# Analog_Project_Sem_3.net
KiCad netlist of a schematic drawn in Altium Designer
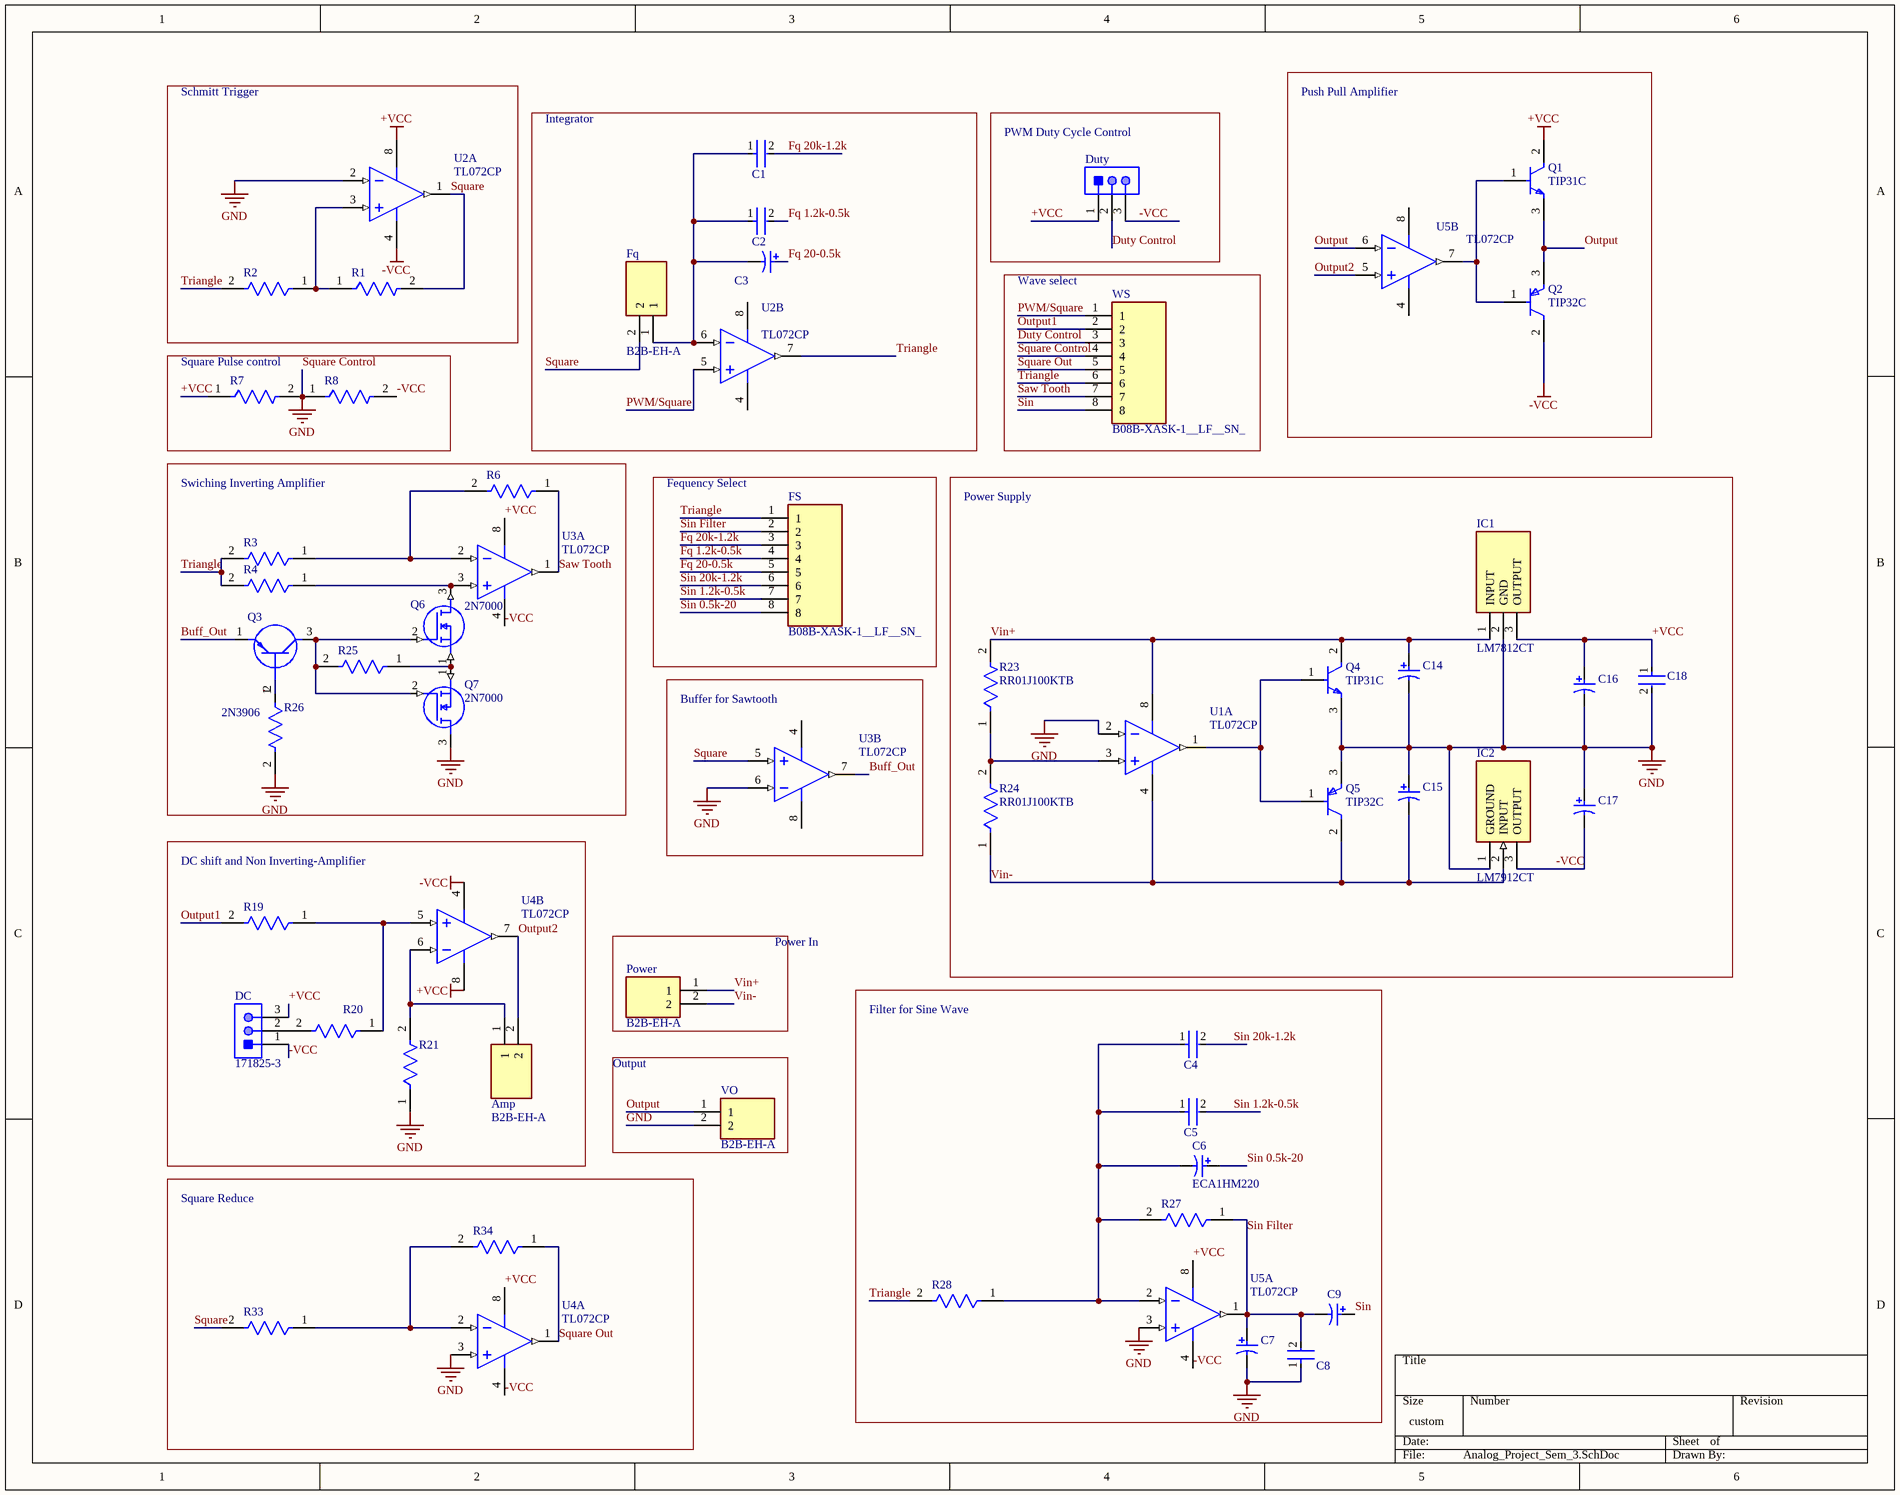
[diagram p0: Analog_Project_Sem_3.SchDoc]

(export (version "E")
  (design (tool "Eeschema 10.0.6"))
  (components
    (comp (ref "Amp")
      (value "B2B-EH-A")
      (footprint "SamacSys:SHDR2W64P0X250_1X2_750X380X600P")
      (description "Connector")
      (libsource (lib "") (part "B2B-EH-A_2"))
    )
    (comp (ref "C1")
      (value "RCER72A104K1A2H03B")
      (footprint "FP-RCE1A2-MFG")
      (description "Cap Ceramic 100nF 100V X7R ±10% Radial 2.5mm +125°C Automotive Bulk")
      (fields (field (name "TOLERANCE") "10%"))
      (libsource (lib "Altium Content Vault") (part "02cd4be3c70576c341d710602a673aa"))
    )
    (comp (ref "C2")
      (value "RCER72A104K1A2H03B")
      (footprint "FP-RCE1A2-MFG")
      (description "Cap Ceramic 100nF 100V X7R ±10% Radial 2.5mm +125°C Automotive Bulk")
      (fields (field (name "TOLERANCE") "10%"))
      (libsource (lib "Altium Content Vault") (part "02cd4be3c70576c341d710602a673aa"))
    )
    (comp (ref "C3")
      (value "ECA1HM220")
      (footprint "CAPPR55-200-1100X500X1200")
      (description "Aluminum Electrolytic Capacitor, 22 uF, +/- 20%, 50 V, -40 to 85 degC, 2-Pin THD, RoHS, Bulk")
      (fields (field (name "VOLTAGE") "50V") (field (name "MANUFACTURER") "Panasonic"))
      (libsource (lib "Altium Content Vault") (part "CAP-P-2"))
    )
    (comp (ref "C4")
      (value "RCER72A104K1A2H03B")
      (footprint "FP-RCE1A2-MFG")
      (description "Cap Ceramic 100nF 100V X7R ±10% Radial 2.5mm +125°C Automotive Bulk")
      (fields (field (name "TOLERANCE") "10%"))
      (libsource (lib "Altium Content Vault") (part "02cd4be3c70576c341d710602a673aa"))
    )
    (comp (ref "C5")
      (value "RCER72A104K1A2H03B")
      (footprint "FP-RCE1A2-MFG")
      (description "Cap Ceramic 100nF 100V X7R ±10% Radial 2.5mm +125°C Automotive Bulk")
      (fields (field (name "TOLERANCE") "10%"))
      (libsource (lib "Altium Content Vault") (part "02cd4be3c70576c341d710602a673aa"))
    )
    (comp (ref "C6")
      (value "ECA1HM220")
      (footprint "CAPPR55-200-1100X500X1200")
      (description "Aluminum Electrolytic Capacitor, 22 uF, +/- 20%, 50 V, -40 to 85 degC, 2-Pin THD, RoHS, Bulk")
      (fields (field (name "VOLTAGE") "50V") (field (name "MANUFACTURER") "Panasonic"))
      (libsource (lib "Altium Content Vault") (part "CAP-P-2"))
    )
    (comp (ref "C7")
      (value "ECA1HM220")
      (footprint "CAPPR55-200-1100X500X1200")
      (description "Aluminum Electrolytic Capacitor, 22 uF, +/- 20%, 50 V, -40 to 85 degC, 2-Pin THD, RoHS, Bulk")
      (fields (field (name "VOLTAGE") "50V") (field (name "MANUFACTURER") "Panasonic"))
      (libsource (lib "Altium Content Vault") (part "CAP-P-2"))
    )
    (comp (ref "C8")
      (value "RCER72A104K1A2H03B")
      (footprint "FP-RCE1A2-MFG")
      (description "Cap Ceramic 100nF 100V X7R ±10% Radial 2.5mm +125°C Automotive Bulk")
      (fields (field (name "TOLERANCE") "10%"))
      (libsource (lib "Altium Content Vault") (part "02cd4be3c70576c341d710602a673aa"))
    )
    (comp (ref "C9")
      (value "ECA1HM220")
      (footprint "CAPPR55-200-1100X500X1200")
      (description "Aluminum Electrolytic Capacitor, 22 uF, +/- 20%, 50 V, -40 to 85 degC, 2-Pin THD, RoHS, Bulk")
      (fields (field (name "VOLTAGE") "50V") (field (name "MANUFACTURER") "Panasonic"))
      (libsource (lib "Altium Content Vault") (part "CAP-P-2"))
    )
    (comp (ref "C14")
      (value "ECA1HM220")
      (footprint "CAPPR55-200-1100X500X1200")
      (description "Aluminum Electrolytic Capacitor, 22 uF, +/- 20%, 50 V, -40 to 85 degC, 2-Pin THD, RoHS, Bulk")
      (fields (field (name "VOLTAGE") "50V") (field (name "MANUFACTURER") "Panasonic"))
      (libsource (lib "Altium Content Vault") (part "CAP-P-2"))
    )
    (comp (ref "C15")
      (value "ECA1HM220")
      (footprint "CAPPR55-200-1100X500X1200")
      (description "Aluminum Electrolytic Capacitor, 22 uF, +/- 20%, 50 V, -40 to 85 degC, 2-Pin THD, RoHS, Bulk")
      (fields (field (name "VOLTAGE") "50V") (field (name "MANUFACTURER") "Panasonic"))
      (libsource (lib "Altium Content Vault") (part "CAP-P-2"))
    )
    (comp (ref "C16")
      (value "ECA1HM220")
      (footprint "CAPPR55-200-1100X500X1200")
      (description "Aluminum Electrolytic Capacitor, 22 uF, +/- 20%, 50 V, -40 to 85 degC, 2-Pin THD, RoHS, Bulk")
      (fields (field (name "VOLTAGE") "50V") (field (name "MANUFACTURER") "Panasonic"))
      (libsource (lib "Altium Content Vault") (part "CAP-P-2"))
    )
    (comp (ref "C17")
      (value "ECA1HM220")
      (footprint "CAPPR55-200-1100X500X1200")
      (description "Aluminum Electrolytic Capacitor, 22 uF, +/- 20%, 50 V, -40 to 85 degC, 2-Pin THD, RoHS, Bulk")
      (fields (field (name "VOLTAGE") "50V") (field (name "MANUFACTURER") "Panasonic"))
      (libsource (lib "Altium Content Vault") (part "CAP-P-2"))
    )
    (comp (ref "C18")
      (value "RCER72A104K1A2H03B")
      (footprint "FP-RCE1A2-MFG")
      (description "Cap Ceramic 100nF 100V X7R ±10% Radial 2.5mm +125°C Automotive Bulk")
      (fields (field (name "TOLERANCE") "10%"))
      (libsource (lib "Altium Content Vault") (part "02cd4be3c70576c341d710602a673aa"))
    )
    (comp (ref "DC")
      (value "171825-3")
      (footprint "TECO-171825-3_V")
      (fields (field (name "MANUFACTURER") "TE Connectivity"))
      (libsource (lib "") (part "CN-1P-M-R3_1"))
    )
    (comp (ref "Duty")
      (value "171825-3")
      (footprint "TECO-171825-3_V")
      (fields (field (name "MANUFACTURER") "TE Connectivity"))
      (libsource (lib "Altium Content Vault") (part "CN-1P-M-R3"))
    )
    (comp (ref "Fq")
      (value "B2B-EH-A")
      (footprint "SamacSys:SHDR2W64P0X250_1X2_750X380X600P")
      (description "Connector")
      (libsource (lib "*") (part "B2B-EH-A"))
    )
    (comp (ref "FS")
      (value "B08B-XASK-1__LF__SN_")
      (footprint "SamacSys:SHDR8W60P0X250_1X8_2250X640X880P")
      (description "Connector")
      (fields (field (name "MANUFACTURER_PART_NUMBER") "B08B-XASK-1 (LF)(SN)"))
      (libsource (lib "*") (part "B08B-XASK-1__LF__SN_"))
    )
    (comp (ref "IC1")
      (value "LM7812CT")
      (footprint "SamacSys:TO254P470X1016X2019-3P")
      (description "Integrated Circuit")
      (fields (field (name "MOUSER PART NUMBER") "512-LM7812CT"))
      (libsource (lib "*") (part "LM7812CT"))
    )
    (comp (ref "IC2")
      (value "LM7912CT")
      (footprint "SamacSys:TO254P483X1016X2261-3P")
      (description "Power Supply")
      (fields (field (name "MOUSER PART NUMBER") "512-LM7912CT"))
      (libsource (lib "*") (part "LM7912CT"))
    )
    (comp (ref "Power")
      (value "B2B-EH-A")
      (footprint "SamacSys:SHDR2W64P0X250_1X2_750X380X600P")
      (description "Connector")
      (libsource (lib "") (part "B2B-EH-A_1"))
    )
    (comp (ref "Q1")
      (value "TIP31C")
      (footprint "FP-TO-220-P0A0015988-MFG")
      (description "TRANS NPN 100V 3A TO-220")
      (fields
        (field (name "OCTOPART") "https://octopart.com/tip31c-stmicroelectronics-15555")
        (field (name "MANUFACTURER") "STMicroelectronics")
      )
      (libsource (lib "Altium Content Vault") (part "1c57d9dae74fe2702546667b0e849db"))
    )
    (comp (ref "Q2")
      (value "TIP32C")
      (footprint "FP-TO-220-P0A0015988-MFG")
      (description "TRANS PNP 100V 3A TO-220")
      (fields
        (field (name "MANUFACTURER") "STMicroelectronics")
        (field (name "OCTOPART") "https://octopart.com/tip32c-stmicroelectronics-353617")
      )
      (libsource (lib "Altium Content Vault") (part "802a31d42ca070764d097f06bc9597f"))
    )
    (comp (ref "Q3")
      (value "2N3906")
      (footprint "SamacSys:2N5457")
      (description "Transistor BJT PNP")
      (fields (field (name "MOUSER PART NUMBER") "610-2N3906"))
      (libsource (lib "*") (part "2N3906"))
    )
    (comp (ref "Q4")
      (value "TIP31C")
      (footprint "FP-TO-220-P0A0015988-MFG")
      (description "TRANS NPN 100V 3A TO-220")
      (fields
        (field (name "OCTOPART") "https://octopart.com/tip31c-stmicroelectronics-15555")
        (field (name "MANUFACTURER") "STMicroelectronics")
      )
      (libsource (lib "Altium Content Vault") (part "1c57d9dae74fe2702546667b0e849db"))
    )
    (comp (ref "Q5")
      (value "TIP32C")
      (footprint "FP-TO-220-P0A0015988-MFG")
      (description "TRANS PNP 100V 3A TO-220")
      (fields
        (field (name "MANUFACTURER") "STMicroelectronics")
        (field (name "OCTOPART") "https://octopart.com/tip32c-stmicroelectronics-353617")
      )
      (libsource (lib "Altium Content Vault") (part "802a31d42ca070764d097f06bc9597f"))
    )
    (comp (ref "Q6")
      (value "2N7000")
      (footprint "SamacSys:TO-92_(TO-226)")
      (description "MOSFET (N-Channel)")
      (fields (field (name "MOUSER PART NUMBER") "512-2N7000"))
      (libsource (lib "*") (part "2N7000"))
    )
    (comp (ref "Q7")
      (value "2N7000")
      (footprint "SamacSys:TO-92_(TO-226)")
      (description "MOSFET (N-Channel)")
      (fields (field (name "MOUSER PART NUMBER") "512-2N7000"))
      (libsource (lib "*") (part "2N7000"))
    )
    (comp (ref "R1")
      (value "~")
      (footprint "FP-MRS1600-MFG")
      (description "RES 20K OHM 0.4W 1% AXIAL")
      (fields (field (name "TOLERANCE") "1%"))
      (libsource (lib "Altium Content Vault") (part "1029c3af85768c4190bb7ad29bc67b5"))
    )
    (comp (ref "R2")
      (value "~")
      (footprint "FP-MRS1600-MFG")
      (description "RES 20K OHM 0.4W 1% AXIAL")
      (fields (field (name "TOLERANCE") "1%"))
      (libsource (lib "Altium Content Vault") (part "1029c3af85768c4190bb7ad29bc67b5"))
    )
    (comp (ref "R3")
      (value "~")
      (footprint "FP-MRS1600-MFG")
      (description "RES 20K OHM 0.4W 1% AXIAL")
      (fields (field (name "TOLERANCE") "1%"))
      (libsource (lib "Altium Content Vault") (part "1029c3af85768c4190bb7ad29bc67b5"))
    )
    (comp (ref "R4")
      (value "~")
      (footprint "FP-MRS1600-MFG")
      (description "RES 20K OHM 0.4W 1% AXIAL")
      (fields (field (name "TOLERANCE") "1%"))
      (libsource (lib "Altium Content Vault") (part "1029c3af85768c4190bb7ad29bc67b5"))
    )
    (comp (ref "R6")
      (value "~")
      (footprint "FP-MRS1600-MFG")
      (description "RES 20K OHM 0.4W 1% AXIAL")
      (fields (field (name "TOLERANCE") "1%"))
      (libsource (lib "Altium Content Vault") (part "1029c3af85768c4190bb7ad29bc67b5"))
    )
    (comp (ref "R7")
      (value "~")
      (footprint "FP-MRS1600-MFG")
      (description "RES 20K OHM 0.4W 1% AXIAL")
      (fields (field (name "TOLERANCE") "1%"))
      (libsource (lib "Altium Content Vault") (part "1029c3af85768c4190bb7ad29bc67b5"))
    )
    (comp (ref "R8")
      (value "~")
      (footprint "FP-MRS1600-MFG")
      (description "RES 20K OHM 0.4W 1% AXIAL")
      (fields (field (name "TOLERANCE") "1%"))
      (libsource (lib "Altium Content Vault") (part "1029c3af85768c4190bb7ad29bc67b5"))
    )
    (comp (ref "R19")
      (value "~")
      (footprint "FP-MRS1600-MFG")
      (description "RES 20K OHM 0.4W 1% AXIAL")
      (fields (field (name "TOLERANCE") "1%"))
      (libsource (lib "Altium Content Vault") (part "1029c3af85768c4190bb7ad29bc67b5"))
    )
    (comp (ref "R20")
      (value "~")
      (footprint "FP-MRS1600-MFG")
      (description "RES 20K OHM 0.4W 1% AXIAL")
      (fields (field (name "TOLERANCE") "1%"))
      (libsource (lib "Altium Content Vault") (part "1029c3af85768c4190bb7ad29bc67b5"))
    )
    (comp (ref "R21")
      (value "~")
      (footprint "FP-MRS1600-MFG")
      (description "RES 20K OHM 0.4W 1% AXIAL")
      (fields (field (name "TOLERANCE") "1%"))
      (libsource (lib "Altium Content Vault") (part "1029c3af85768c4190bb7ad29bc67b5"))
    )
    (comp (ref "R23")
      (value "RR01J100KTB")
      (footprint "FP-RR01-MFG")
      (description "RES 100K OHM 5% 1W AXIAL")
      (fields (field (name "TOLERANCE") "5%"))
      (libsource (lib "Altium Content Vault") (part "1029c3af85768c4190bb7ad29bc67b5"))
    )
    (comp (ref "R24")
      (value "RR01J100KTB")
      (footprint "FP-RR01-MFG")
      (description "RES 100K OHM 5% 1W AXIAL")
      (fields (field (name "TOLERANCE") "5%"))
      (libsource (lib "Altium Content Vault") (part "1029c3af85768c4190bb7ad29bc67b5"))
    )
    (comp (ref "R25")
      (value "~")
      (footprint "FP-MRS1600-MFG")
      (description "RES 20K OHM 0.4W 1% AXIAL")
      (fields (field (name "TOLERANCE") "1%"))
      (libsource (lib "Altium Content Vault") (part "1029c3af85768c4190bb7ad29bc67b5"))
    )
    (comp (ref "R26")
      (value "~")
      (footprint "FP-MRS1600-MFG")
      (description "RES 20K OHM 0.4W 1% AXIAL")
      (fields (field (name "TOLERANCE") "1%"))
      (libsource (lib "Altium Content Vault") (part "1029c3af85768c4190bb7ad29bc67b5"))
    )
    (comp (ref "R27")
      (value "~")
      (footprint "FP-MRS1600-MFG")
      (description "RES 20K OHM 0.4W 1% AXIAL")
      (fields (field (name "TOLERANCE") "1%"))
      (libsource (lib "Altium Content Vault") (part "1029c3af85768c4190bb7ad29bc67b5"))
    )
    (comp (ref "R28")
      (value "~")
      (footprint "FP-MRS1600-MFG")
      (description "RES 20K OHM 0.4W 1% AXIAL")
      (fields (field (name "TOLERANCE") "1%"))
      (libsource (lib "Altium Content Vault") (part "1029c3af85768c4190bb7ad29bc67b5"))
    )
    (comp (ref "R33")
      (value "~")
      (footprint "FP-MRS1600-MFG")
      (description "RES 20K OHM 0.4W 1% AXIAL")
      (fields (field (name "TOLERANCE") "1%"))
      (libsource (lib "Altium Content Vault") (part "1029c3af85768c4190bb7ad29bc67b5"))
    )
    (comp (ref "R34")
      (value "~")
      (footprint "FP-MRS1600-MFG")
      (description "RES 20K OHM 0.4W 1% AXIAL")
      (fields (field (name "TOLERANCE") "1%"))
      (libsource (lib "Altium Content Vault") (part "1029c3af85768c4190bb7ad29bc67b5"))
    )
    (comp (ref "U1")
      (value "TL072CP")
      (footprint "P0008A")
      (fields (field (name "MANUFACTURER") "Texas Instruments"))
      (libsource (lib "Altium Content Vault") (part "TI-AMP-D6-2-8_D"))
    )
    (comp (ref "U2")
      (value "TL072CP")
      (footprint "P0008A")
      (fields (field (name "MANUFACTURER") "Texas Instruments"))
      (libsource (lib "Altium Content Vault") (part "TI-AMP-D6-2-8_D"))
    )
    (comp (ref "U3")
      (value "TL072CP")
      (footprint "P0008A")
      (fields (field (name "MANUFACTURER") "Texas Instruments"))
      (libsource (lib "Altium Content Vault") (part "TI-AMP-D6-2-8_D"))
    )
    (comp (ref "U4")
      (value "TL072CP")
      (footprint "P0008A")
      (fields (field (name "MANUFACTURER") "Texas Instruments"))
      (libsource (lib "Altium Content Vault") (part "TI-AMP-D6-2-8_D"))
    )
    (comp (ref "U5")
      (value "TL072CP")
      (footprint "P0008A")
      (fields (field (name "MANUFACTURER") "Texas Instruments"))
      (libsource (lib "Altium Content Vault") (part "TI-AMP-D6-2-8_D"))
    )
    (comp (ref "VO")
      (value "B2B-EH-A")
      (footprint "SamacSys:SHDR2W64P0X250_1X2_750X380X600P")
      (description "Connector")
      (libsource (lib "*") (part "B2B-EH-A"))
    )
    (comp (ref "WS")
      (value "B08B-XASK-1__LF__SN_")
      (footprint "SamacSys:SHDR8W60P0X250_1X8_2250X640X880P")
      (description "Connector")
      (fields (field (name "MANUFACTURER_PART_NUMBER") "B08B-XASK-1 (LF)(SN)"))
      (libsource (lib "*") (part "B08B-XASK-1__LF__SN_"))
    )
  )
  (nets
    (net (code "1") (name "+VCC") (class "Default")
      (node (ref "C16") (pin "1") (pinfunction "1_1") (pintype "passive"))
      (node (ref "C18") (pin "1") (pinfunction "1_1") (pintype "passive"))
      (node (ref "DC") (pin "3") (pinfunction "3_3") (pintype "passive"))
      (node (ref "Duty") (pin "1") (pinfunction "1_1") (pintype "passive"))
      (node (ref "IC1") (pin "3") (pinfunction "OUTPUT_3") (pintype "passive"))
      (node (ref "Q1") (pin "2") (pinfunction "C_2") (pintype "passive"))
      (node (ref "R7") (pin "1") (pinfunction "1_1") (pintype "passive"))
      (node (ref "U2") (pin "8") (pinfunction "VCC+_8") (pintype "power_in"))
      (node (ref "U3") (pin "8") (pinfunction "VCC+_8") (pintype "power_in"))
      (node (ref "U4") (pin "8") (pinfunction "VCC+_8") (pintype "power_in"))
      (node (ref "U5") (pin "8") (pinfunction "VCC+_8") (pintype "power_in"))
    )
    (net (code "2") (name "-VCC") (class "Default")
      (node (ref "C17") (pin "2") (pinfunction "2_2") (pintype "passive"))
      (node (ref "DC") (pin "1") (pinfunction "1_1") (pintype "passive"))
      (node (ref "Duty") (pin "3") (pinfunction "3_3") (pintype "passive"))
      (node (ref "IC2") (pin "3") (pinfunction "OUTPUT_3") (pintype "passive"))
      (node (ref "Q2") (pin "2") (pinfunction "C_2") (pintype "passive"))
      (node (ref "R8") (pin "2") (pinfunction "2_2") (pintype "passive"))
      (node (ref "U2") (pin "4") (pinfunction "VCC-_4") (pintype "power_in"))
      (node (ref "U3") (pin "4") (pinfunction "VCC-_4") (pintype "power_in"))
      (node (ref "U4") (pin "4") (pinfunction "VCC-_4") (pintype "power_in"))
      (node (ref "U5") (pin "4") (pinfunction "VCC-_4") (pintype "power_in"))
    )
    (net (code "3") (name "/Buff_Out") (class "Default")
      (node (ref "Q3") (pin "1") (pinfunction "E_1") (pintype "passive"))
      (node (ref "U3") (pin "7") (pinfunction "OUT2_7") (pintype "output"))
    )
    (net (code "4") (name "/Duty Control") (class "Default")
      (node (ref "Duty") (pin "2") (pinfunction "2_2") (pintype "passive"))
      (node (ref "WS") (pin "3") (pinfunction "3_3") (pintype "passive"))
    )
    (net (code "5") (name "/Fq 1.2k-0.5k") (class "Default")
      (node (ref "C2") (pin "2") (pinfunction "2_2") (pintype "passive"))
      (node (ref "FS") (pin "4") (pinfunction "4_4") (pintype "passive"))
    )
    (net (code "6") (name "/Fq 20-0.5k") (class "Default")
      (node (ref "C3") (pin "1") (pinfunction "1_1") (pintype "passive"))
      (node (ref "FS") (pin "5") (pinfunction "5_5") (pintype "passive"))
    )
    (net (code "7") (name "/Fq 20k-1.2k") (class "Default")
      (node (ref "C1") (pin "2") (pinfunction "2_2") (pintype "passive"))
      (node (ref "FS") (pin "3") (pinfunction "3_3") (pintype "passive"))
    )
    (net (code "8") (name "/Output") (class "Default")
      (node (ref "Q1") (pin "3") (pinfunction "E_3") (pintype "passive"))
      (node (ref "Q2") (pin "3") (pinfunction "E_3") (pintype "passive"))
      (node (ref "U5") (pin "6") (pinfunction "IN2-_6") (pintype "input"))
      (node (ref "VO") (pin "1") (pinfunction "1_1") (pintype "passive"))
    )
    (net (code "9") (name "/Output1") (class "Default")
      (node (ref "R19") (pin "2") (pinfunction "2_2") (pintype "passive"))
      (node (ref "WS") (pin "2") (pinfunction "2_2") (pintype "passive"))
    )
    (net (code "10") (name "/Output2") (class "Default")
      (node (ref "Amp") (pin "2") (pinfunction "2_2") (pintype "passive"))
      (node (ref "U4") (pin "7") (pinfunction "OUT2_7") (pintype "output"))
      (node (ref "U5") (pin "5") (pinfunction "IN2+_5") (pintype "input"))
    )
    (net (code "11") (name "/PWM{slash}Square") (class "Default")
      (node (ref "U2") (pin "5") (pinfunction "IN2+_5") (pintype "input"))
      (node (ref "WS") (pin "1") (pinfunction "1_1") (pintype "passive"))
    )
    (net (code "12") (name "/Saw Tooth") (class "Default")
      (node (ref "R6") (pin "1") (pinfunction "1_1") (pintype "passive"))
      (node (ref "U3") (pin "1") (pinfunction "OUT1_1") (pintype "output"))
      (node (ref "WS") (pin "7") (pinfunction "7_7") (pintype "passive"))
    )
    (net (code "13") (name "/Sin") (class "Default")
      (node (ref "C9") (pin "1") (pinfunction "1_1") (pintype "passive"))
      (node (ref "WS") (pin "8") (pinfunction "8_8") (pintype "passive"))
    )
    (net (code "14") (name "/Sin 0.5k-20") (class "Default")
      (node (ref "C6") (pin "1") (pinfunction "1_1") (pintype "passive"))
      (node (ref "FS") (pin "8") (pinfunction "8_8") (pintype "passive"))
    )
    (net (code "15") (name "/Sin 1.2k-0.5k") (class "Default")
      (node (ref "C5") (pin "2") (pinfunction "2_2") (pintype "passive"))
      (node (ref "FS") (pin "7") (pinfunction "7_7") (pintype "passive"))
    )
    (net (code "16") (name "/Sin 20k-1.2k") (class "Default")
      (node (ref "C4") (pin "2") (pinfunction "2_2") (pintype "passive"))
      (node (ref "FS") (pin "6") (pinfunction "6_6") (pintype "passive"))
    )
    (net (code "17") (name "/Sin Filter") (class "Default")
      (node (ref "C7") (pin "1") (pinfunction "1_1") (pintype "passive"))
      (node (ref "C8") (pin "2") (pinfunction "2_2") (pintype "passive"))
      (node (ref "C9") (pin "2") (pinfunction "2_2") (pintype "passive"))
      (node (ref "FS") (pin "2") (pinfunction "2_2") (pintype "passive"))
      (node (ref "R27") (pin "1") (pinfunction "1_1") (pintype "passive"))
      (node (ref "U5") (pin "1") (pinfunction "OUT1_1") (pintype "output"))
    )
    (net (code "18") (name "/Square") (class "Default")
      (node (ref "Fq") (pin "2") (pinfunction "2_2") (pintype "passive"))
      (node (ref "R1") (pin "2") (pinfunction "2_2") (pintype "passive"))
      (node (ref "R33") (pin "2") (pinfunction "2_2") (pintype "passive"))
      (node (ref "U2") (pin "1") (pinfunction "OUT1_1") (pintype "output"))
      (node (ref "U3") (pin "5") (pinfunction "IN2+_5") (pintype "input"))
    )
    (net (code "19") (name "/Square Out") (class "Default")
      (node (ref "R34") (pin "1") (pinfunction "1_1") (pintype "passive"))
      (node (ref "U4") (pin "1") (pinfunction "OUT1_1") (pintype "output"))
      (node (ref "WS") (pin "5") (pinfunction "5_5") (pintype "passive"))
    )
    (net (code "20") (name "/Triangle") (class "Default")
      (node (ref "FS") (pin "1") (pinfunction "1_1") (pintype "passive"))
      (node (ref "R2") (pin "2") (pinfunction "2_2") (pintype "passive"))
      (node (ref "R28") (pin "2") (pinfunction "2_2") (pintype "passive"))
      (node (ref "R3") (pin "2") (pinfunction "2_2") (pintype "passive"))
      (node (ref "R4") (pin "2") (pinfunction "2_2") (pintype "passive"))
      (node (ref "U2") (pin "7") (pinfunction "OUT2_7") (pintype "output"))
      (node (ref "WS") (pin "6") (pinfunction "6_6") (pintype "passive"))
    )
    (net (code "21") (name "/Vin+") (class "Default")
      (node (ref "C14") (pin "1") (pinfunction "1_1") (pintype "passive"))
      (node (ref "IC1") (pin "1") (pinfunction "INPUT_1") (pintype "passive"))
      (node (ref "Power") (pin "1") (pinfunction "1_1") (pintype "passive"))
      (node (ref "Q4") (pin "2") (pinfunction "C_2") (pintype "passive"))
      (node (ref "R23") (pin "2") (pinfunction "2_2") (pintype "passive"))
      (node (ref "U1") (pin "8") (pinfunction "VCC+_8") (pintype "power_in"))
    )
    (net (code "22") (name "/Vin-") (class "Default")
      (node (ref "C15") (pin "2") (pinfunction "2_2") (pintype "passive"))
      (node (ref "IC2") (pin "2") (pinfunction "INPUT_2") (pintype "input"))
      (node (ref "Power") (pin "2") (pinfunction "2_2") (pintype "passive"))
      (node (ref "Q5") (pin "2") (pinfunction "C_2") (pintype "passive"))
      (node (ref "R24") (pin "1") (pinfunction "1_1") (pintype "passive"))
      (node (ref "U1") (pin "4") (pinfunction "VCC-_4") (pintype "power_in"))
    )
    (net (code "23") (name "GND") (class "Default")
      (node (ref "C14") (pin "2") (pinfunction "2_2") (pintype "passive"))
      (node (ref "C15") (pin "1") (pinfunction "1_1") (pintype "passive"))
      (node (ref "C16") (pin "2") (pinfunction "2_2") (pintype "passive"))
      (node (ref "C17") (pin "1") (pinfunction "1_1") (pintype "passive"))
      (node (ref "C18") (pin "2") (pinfunction "2_2") (pintype "passive"))
      (node (ref "C7") (pin "2") (pinfunction "2_2") (pintype "passive"))
      (node (ref "C8") (pin "1") (pinfunction "1_1") (pintype "passive"))
      (node (ref "IC1") (pin "2") (pinfunction "GND_2") (pintype "passive"))
      (node (ref "IC2") (pin "1") (pinfunction "GROUND_1") (pintype "power_in"))
      (node (ref "Q4") (pin "3") (pinfunction "E_3") (pintype "passive"))
      (node (ref "Q5") (pin "3") (pinfunction "E_3") (pintype "passive"))
      (node (ref "Q7") (pin "3") (pinfunction "D_3") (pintype "output"))
      (node (ref "R21") (pin "1") (pinfunction "1_1") (pintype "passive"))
      (node (ref "R26") (pin "2") (pinfunction "2_2") (pintype "passive"))
      (node (ref "R7") (pin "2") (pinfunction "2_2") (pintype "passive"))
      (node (ref "R8") (pin "1") (pinfunction "1_1") (pintype "passive"))
      (node (ref "U1") (pin "2") (pinfunction "IN1-_2") (pintype "input"))
      (node (ref "U2") (pin "2") (pinfunction "IN1-_2") (pintype "input"))
      (node (ref "U3") (pin "6") (pinfunction "IN2-_6") (pintype "input"))
      (node (ref "U4") (pin "3") (pinfunction "IN1+_3") (pintype "input"))
      (node (ref "U5") (pin "3") (pinfunction "IN1+_3") (pintype "input"))
      (node (ref "VO") (pin "2") (pinfunction "2_2") (pintype "passive"))
      (node (ref "WS") (pin "4") (pinfunction "4_4") (pintype "passive"))
    )
    (net (code "24") (name "Net-(DC-Pad2)") (class "Default")
      (node (ref "DC") (pin "2") (pinfunction "2_2") (pintype "passive"))
      (node (ref "R20") (pin "2") (pinfunction "2_2") (pintype "passive"))
    )
    (net (code "25") (name "Net-(Q1-B)") (class "Default")
      (node (ref "Q1") (pin "1") (pinfunction "B_1") (pintype "passive"))
      (node (ref "Q2") (pin "1") (pinfunction "B_1") (pintype "passive"))
      (node (ref "U5") (pin "7") (pinfunction "OUT2_7") (pintype "output"))
    )
    (net (code "26") (name "Net-(Q3-B)") (class "Default")
      (node (ref "Q3") (pin "2") (pinfunction "B_2") (pintype "passive"))
      (node (ref "R26") (pin "1") (pinfunction "1_1") (pintype "passive"))
    )
    (net (code "27") (name "Net-(Q3-C)") (class "Default")
      (node (ref "Q3") (pin "3") (pinfunction "C_3") (pintype "passive"))
      (node (ref "Q6") (pin "2") (pinfunction "G_2") (pintype "input"))
      (node (ref "Q7") (pin "2") (pinfunction "G_2") (pintype "input"))
      (node (ref "R25") (pin "2") (pinfunction "2_2") (pintype "passive"))
    )
    (net (code "28") (name "Net-(Q4-B)") (class "Default")
      (node (ref "Q4") (pin "1") (pinfunction "B_1") (pintype "passive"))
      (node (ref "Q5") (pin "1") (pinfunction "B_1") (pintype "passive"))
      (node (ref "U1") (pin "1") (pinfunction "OUT1_1") (pintype "output"))
    )
    (net (code "29") (name "Net-(Q6-D)") (class "Default")
      (node (ref "Q6") (pin "3") (pinfunction "D_3") (pintype "output"))
      (node (ref "R4") (pin "1") (pinfunction "1_1") (pintype "passive"))
      (node (ref "U3") (pin "3") (pinfunction "IN1+_3") (pintype "input"))
    )
    (net (code "30") (name "Net-(Q6-S)") (class "Default")
      (node (ref "Q6") (pin "1") (pinfunction "S_1") (pintype "input"))
      (node (ref "Q7") (pin "1") (pinfunction "S_1") (pintype "input"))
      (node (ref "R25") (pin "1") (pinfunction "1_1") (pintype "passive"))
    )
    (net (code "31") (name "Net-(U1A-IN1+)") (class "Default")
      (node (ref "R23") (pin "1") (pinfunction "1_1") (pintype "passive"))
      (node (ref "R24") (pin "2") (pinfunction "2_2") (pintype "passive"))
      (node (ref "U1") (pin "3") (pinfunction "IN1+_3") (pintype "input"))
    )
    (net (code "32") (name "Net-(U2A-IN1+)") (class "Default")
      (node (ref "R1") (pin "1") (pinfunction "1_1") (pintype "passive"))
      (node (ref "R2") (pin "1") (pinfunction "1_1") (pintype "passive"))
      (node (ref "U2") (pin "3") (pinfunction "IN1+_3") (pintype "input"))
    )
    (net (code "33") (name "Net-(U2B-IN2-)") (class "Default")
      (node (ref "C1") (pin "1") (pinfunction "1_1") (pintype "passive"))
      (node (ref "C2") (pin "1") (pinfunction "1_1") (pintype "passive"))
      (node (ref "C3") (pin "2") (pinfunction "2_2") (pintype "passive"))
      (node (ref "Fq") (pin "1") (pinfunction "1_1") (pintype "passive"))
      (node (ref "U2") (pin "6") (pinfunction "IN2-_6") (pintype "input"))
    )
    (net (code "34") (name "Net-(U3A-IN1-)") (class "Default")
      (node (ref "R3") (pin "1") (pinfunction "1_1") (pintype "passive"))
      (node (ref "R6") (pin "2") (pinfunction "2_2") (pintype "passive"))
      (node (ref "U3") (pin "2") (pinfunction "IN1-_2") (pintype "input"))
    )
    (net (code "35") (name "Net-(U4A-IN1-)") (class "Default")
      (node (ref "R33") (pin "1") (pinfunction "1_1") (pintype "passive"))
      (node (ref "R34") (pin "2") (pinfunction "2_2") (pintype "passive"))
      (node (ref "U4") (pin "2") (pinfunction "IN1-_2") (pintype "input"))
    )
    (net (code "36") (name "Net-(U4B-IN2+)") (class "Default")
      (node (ref "R19") (pin "1") (pinfunction "1_1") (pintype "passive"))
      (node (ref "R20") (pin "1") (pinfunction "1_1") (pintype "passive"))
      (node (ref "U4") (pin "5") (pinfunction "IN2+_5") (pintype "input"))
    )
    (net (code "37") (name "Net-(U4B-IN2-)") (class "Default")
      (node (ref "Amp") (pin "1") (pinfunction "1_1") (pintype "passive"))
      (node (ref "R21") (pin "2") (pinfunction "2_2") (pintype "passive"))
      (node (ref "U4") (pin "6") (pinfunction "IN2-_6") (pintype "input"))
    )
    (net (code "38") (name "Net-(U5A-IN1-)") (class "Default")
      (node (ref "C4") (pin "1") (pinfunction "1_1") (pintype "passive"))
      (node (ref "C5") (pin "1") (pinfunction "1_1") (pintype "passive"))
      (node (ref "C6") (pin "2") (pinfunction "2_2") (pintype "passive"))
      (node (ref "R27") (pin "2") (pinfunction "2_2") (pintype "passive"))
      (node (ref "R28") (pin "1") (pinfunction "1_1") (pintype "passive"))
      (node (ref "U5") (pin "2") (pinfunction "IN1-_2") (pintype "input"))
    )
    (net (code "39") (name "unconnected-(U2B-VCC+-Pad8)") (class "Default")
      (node (ref "U2") (pin "8") (pinfunction "VCC+_8") (pintype "power_in"))
    )
    (net (code "40") (name "unconnected-(U2B-VCC--Pad4)") (class "Default")
      (node (ref "U2") (pin "4") (pinfunction "VCC-_4") (pintype "power_in"))
    )
    (net (code "41") (name "unconnected-(U3B-VCC+-Pad8)") (class "Default")
      (node (ref "U3") (pin "8") (pinfunction "VCC+_8") (pintype "power_in"))
    )
    (net (code "42") (name "unconnected-(U3B-VCC--Pad4)") (class "Default")
      (node (ref "U3") (pin "4") (pinfunction "VCC-_4") (pintype "power_in"))
    )
    (net (code "43") (name "unconnected-(U5B-VCC+-Pad8)") (class "Default")
      (node (ref "U5") (pin "8") (pinfunction "VCC+_8") (pintype "power_in"))
    )
    (net (code "44") (name "unconnected-(U5B-VCC--Pad4)") (class "Default")
      (node (ref "U5") (pin "4") (pinfunction "VCC-_4") (pintype "power_in"))
    )
  )
)
